# controller.net
KiCad netlist of a schematic drawn in EAGLE
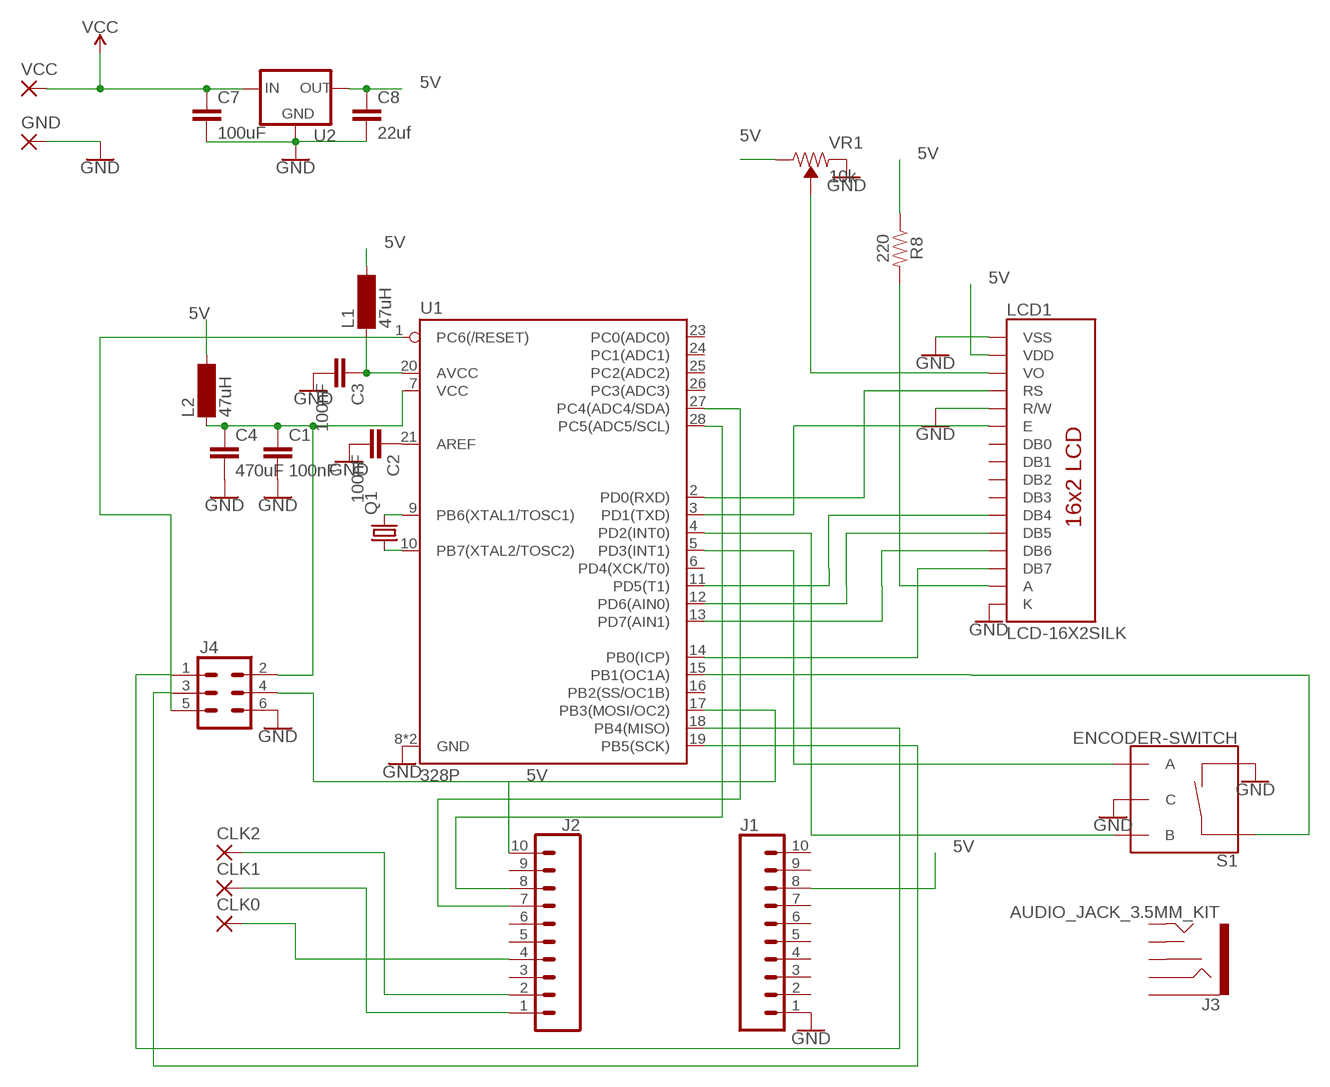
[diagram p0: schematic, sheet 1]

(export (version "E")
  (design (tool "Eeschema 10.0.6"))
  (components
    (comp (ref "C1")
      (value "100nF")
      (footprint "eagle-import:C5B3.5")
      (libsource (lib "eagle-import") (part "C5/3.5"))
    )
    (comp (ref "C2")
      (value "100nF")
      (footprint "eagle-import:C5B3.5")
      (libsource (lib "eagle-import") (part "C5/3.5"))
    )
    (comp (ref "C3")
      (value "100nF")
      (footprint "eagle-import:C5B3.5")
      (libsource (lib "eagle-import") (part "C5/3.5"))
    )
    (comp (ref "C4")
      (value "470uF")
      (footprint "eagle-import:C5B3.5")
      (libsource (lib "eagle-import") (part "C5/3.5"))
    )
    (comp (ref "C7")
      (value "100uF")
      (footprint "eagle-import:C5B3.5")
      (libsource (lib "eagle-import") (part "C5/3.5"))
    )
    (comp (ref "C8")
      (value "22uf")
      (footprint "eagle-import:C5B3.5")
      (libsource (lib "eagle-import") (part "C5/3.5"))
    )
    (comp (ref "CLK0")
      (value "3,17/1,1")
      (footprint "eagle-import:3,17_1,1")
      (libsource (lib "eagle-import") (part "3,17/1,1"))
    )
    (comp (ref "CLK1")
      (value "3,17/1,1")
      (footprint "eagle-import:3,17_1,1")
      (libsource (lib "eagle-import") (part "3,17/1,1"))
    )
    (comp (ref "CLK2")
      (value "3,17/1,1")
      (footprint "eagle-import:3,17_1,1")
      (libsource (lib "eagle-import") (part "3,17/1,1"))
    )
    (comp (ref "GND")
      (value "3,17/1,1")
      (footprint "eagle-import:3,17_1,1")
      (libsource (lib "eagle-import") (part "3,17/1,1"))
    )
    (comp (ref "J1")
      (value "CONN_10NO_SILK_PTH_FEMALE")
      (footprint "eagle-import:1X10_NO_SILK")
      (libsource (lib "eagle-import") (part "CONN_10NO_SILK_PTH_FEMALE"))
    )
    (comp (ref "J2")
      (value "CONN_10NO_SILK_PTH_FEMALE")
      (footprint "eagle-import:1X10_NO_SILK")
      (libsource (lib "eagle-import") (part "CONN_10NO_SILK_PTH_FEMALE"))
    )
    (comp (ref "J3")
      (value "AUDIO_JACK_3.5MM_KIT")
      (footprint "eagle-import:AUDIO-JACK-KIT")
      (libsource (lib "eagle-import") (part "AUDIO_JACK_3.5MM_KIT"))
    )
    (comp (ref "J4")
      (value "CONN_03X2NO_SILK")
      (footprint "eagle-import:2X3-NS")
      (libsource (lib "eagle-import") (part "CONN_03X2NO_SILK"))
    )
    (comp (ref "L1")
      (value "47uH")
      (footprint "eagle-import:BS75")
      (libsource (lib "eagle-import") (part "BS75"))
    )
    (comp (ref "L2")
      (value "47uH")
      (footprint "eagle-import:BS75")
      (libsource (lib "eagle-import") (part "BS75"))
    )
    (comp (ref "LCD1")
      (value "LCD-16X2SILK")
      (footprint "eagle-import:LCD-16X2")
      (libsource (lib "eagle-import") (part "LCD-16X2SILK"))
    )
    (comp (ref "Q1")
      (value "CRYTALHC49S")
      (footprint "eagle-import:HC49_S")
      (libsource (lib "eagle-import") (part "CRYTALHC49S"))
    )
    (comp (ref "R8")
      (value "220")
      (footprint "eagle-import:AXIAL-0.3")
      (libsource (lib "eagle-import") (part "1KOHM-HORIZ-1/4W-1%"))
    )
    (comp (ref "S1")
      (value "ENCODER-SWITCH")
      (footprint "eagle-import:ROTARY_ENC_PLAIN")
      (libsource (lib "eagle-import") (part "ENCODER-SWITCH"))
    )
    (comp (ref "U1")
      (value "328P")
      (footprint "eagle-import:DIP28")
      (libsource (lib "eagle-import") (part "ATMEGA328P_PDIP"))
    )
    (comp (ref "U2")
      (value "V_REG_78XXSINK")
      (footprint "eagle-import:TO220-IGO")
      (libsource (lib "eagle-import") (part "V_REG_78XXSINK"))
    )
    (comp (ref "VCC")
      (value "3,17/1,1")
      (footprint "eagle-import:3,17_1,1")
      (libsource (lib "eagle-import") (part "3,17/1,1"))
    )
    (comp (ref "VR1")
      (value "10k")
      (footprint "eagle-import:TRIMPOT-PTH-3386U")
      (libsource (lib "eagle-import") (part "TRIMPOT-PTH-10MM-KNOB-1/2W-10%"))
    )
  )
  (nets
    (net (code "1") (name "/5V") (class "Default")
      (node (ref "C8") (pin "1") (pinfunction "1_1") (pintype "passive"))
      (node (ref "J1") (pin "8") (pinfunction "8_8") (pintype "passive"))
      (node (ref "J2") (pin "10") (pinfunction "10_10") (pintype "passive"))
      (node (ref "L1") (pin "2") (pinfunction "2_2") (pintype "passive"))
      (node (ref "L2") (pin "2") (pinfunction "2_2") (pintype "passive"))
      (node (ref "LCD1") (pin "2") (pinfunction "VDD_2") (pintype "power_in"))
      (node (ref "R8") (pin "P$1") (pinfunction "1_P$1") (pintype "passive"))
      (node (ref "U2") (pin "OUT") (pinfunction "OUT_OUT") (pintype "passive"))
      (node (ref "VR1") (pin "3") (pinfunction "CW_3") (pintype "passive"))
    )
    (net (code "2") (name "GND") (class "Default")
      (node (ref "C1") (pin "2") (pinfunction "2_2") (pintype "passive"))
      (node (ref "C2") (pin "2") (pinfunction "2_2") (pintype "passive"))
      (node (ref "C3") (pin "2") (pinfunction "2_2") (pintype "passive"))
      (node (ref "C4") (pin "2") (pinfunction "2_2") (pintype "passive"))
      (node (ref "C7") (pin "2") (pinfunction "2_2") (pintype "passive"))
      (node (ref "C8") (pin "2") (pinfunction "2_2") (pintype "passive"))
      (node (ref "GND") (pin "1") (pinfunction "P_1") (pintype "passive"))
      (node (ref "J1") (pin "1") (pinfunction "1_1") (pintype "passive"))
      (node (ref "J4") (pin "6") (pinfunction "6_6") (pintype "bidirectional"))
      (node (ref "LCD1") (pin "1") (pinfunction "VSS_1") (pintype "power_in"))
      (node (ref "LCD1") (pin "16") (pinfunction "K_16") (pintype "power_in"))
      (node (ref "LCD1") (pin "5") (pinfunction "R/W_5") (pintype "input"))
      (node (ref "S1") (pin "C") (pinfunction "C_C") (pintype "bidirectional"))
      (node (ref "S1") (pin "SW-") (pinfunction "SW-_SW-") (pintype "bidirectional"))
      (node (ref "U1") (pin "22") (pinfunction "GND_22") (pintype "bidirectional"))
      (node (ref "U1") (pin "8") (pinfunction "GND_8") (pintype "bidirectional"))
      (node (ref "U2") (pin "GND") (pinfunction "GND_GND") (pintype "input"))
      (node (ref "VR1") (pin "1") (pinfunction "CCW_1") (pintype "passive"))
    )
    (net (code "3") (name "Net-(CLK0-P)") (class "Default")
      (node (ref "CLK0") (pin "1") (pinfunction "P_1") (pintype "passive"))
      (node (ref "J2") (pin "4") (pinfunction "4_4") (pintype "passive"))
    )
    (net (code "4") (name "Net-(CLK1-P)") (class "Default")
      (node (ref "CLK1") (pin "1") (pinfunction "P_1") (pintype "passive"))
      (node (ref "J2") (pin "1") (pinfunction "1_1") (pintype "passive"))
    )
    (net (code "5") (name "Net-(CLK2-P)") (class "Default")
      (node (ref "CLK2") (pin "1") (pinfunction "P_1") (pintype "passive"))
      (node (ref "J2") (pin "2") (pinfunction "2_2") (pintype "passive"))
    )
    (net (code "6") (name "Net-(LCD1-A)") (class "Default")
      (node (ref "LCD1") (pin "15") (pinfunction "A_15") (pintype "power_in"))
      (node (ref "R8") (pin "P$2") (pinfunction "2_P$2") (pintype "passive"))
    )
    (net (code "7") (name "Net-(LCD1-DB4)") (class "Default")
      (node (ref "LCD1") (pin "11") (pinfunction "DB4_11") (pintype "bidirectional"))
      (node (ref "U1") (pin "11") (pinfunction "PD5(T1)_11") (pintype "bidirectional"))
    )
    (net (code "8") (name "Net-(LCD1-DB5)") (class "Default")
      (node (ref "LCD1") (pin "12") (pinfunction "DB5_12") (pintype "bidirectional"))
      (node (ref "U1") (pin "12") (pinfunction "PD6(AIN0)_12") (pintype "bidirectional"))
    )
    (net (code "9") (name "Net-(LCD1-DB6)") (class "Default")
      (node (ref "LCD1") (pin "13") (pinfunction "DB6_13") (pintype "bidirectional"))
      (node (ref "U1") (pin "13") (pinfunction "PD7(AIN1)_13") (pintype "bidirectional"))
    )
    (net (code "10") (name "Net-(LCD1-DB7)") (class "Default")
      (node (ref "LCD1") (pin "14") (pinfunction "DB7_14") (pintype "bidirectional"))
      (node (ref "U1") (pin "14") (pinfunction "PB0(ICP)_14") (pintype "bidirectional"))
    )
    (net (code "11") (name "Net-(LCD1-E)") (class "Default")
      (node (ref "LCD1") (pin "6") (pinfunction "E_6") (pintype "input"))
      (node (ref "U1") (pin "3") (pinfunction "PD1(TXD)_3") (pintype "bidirectional"))
    )
    (net (code "12") (name "Net-(LCD1-RS)") (class "Default")
      (node (ref "LCD1") (pin "4") (pinfunction "RS_4") (pintype "input"))
      (node (ref "U1") (pin "2") (pinfunction "PD0(RXD)_2") (pintype "bidirectional"))
    )
    (net (code "13") (name "Net-(LCD1-VO)") (class "Default")
      (node (ref "LCD1") (pin "3") (pinfunction "VO_3") (pintype "bidirectional"))
      (node (ref "VR1") (pin "2") (pinfunction "WIPER_2") (pintype "passive"))
    )
    (net (code "14") (name "Net-(U1-AREF)") (class "Default")
      (node (ref "C2") (pin "1") (pinfunction "1_1") (pintype "passive"))
      (node (ref "U1") (pin "21") (pinfunction "AREF_21") (pintype "bidirectional"))
    )
    (net (code "15") (name "Net-(U1-AVCC)") (class "Default")
      (node (ref "C3") (pin "1") (pinfunction "1_1") (pintype "passive"))
      (node (ref "L1") (pin "1") (pinfunction "1_1") (pintype "passive"))
      (node (ref "U1") (pin "20") (pinfunction "AVCC_20") (pintype "bidirectional"))
    )
    (net (code "16") (name "Net-(U1-PB1(OC1A))") (class "Default")
      (node (ref "S1") (pin "SW+") (pinfunction "SW+_SW+") (pintype "bidirectional"))
      (node (ref "U1") (pin "15") (pinfunction "PB1(OC1A)_15") (pintype "bidirectional"))
    )
    (net (code "17") (name "Net-(U1-PB3(MOSI{slash}OC2))") (class "Default")
      (node (ref "J4") (pin "4") (pinfunction "4_4") (pintype "bidirectional"))
      (node (ref "U1") (pin "17") (pinfunction "PB3(MOSI/OC2)_17") (pintype "bidirectional"))
    )
    (net (code "18") (name "Net-(U1-PB4(MISO))") (class "Default")
      (node (ref "J4") (pin "1") (pinfunction "1_1") (pintype "bidirectional"))
      (node (ref "U1") (pin "18") (pinfunction "PB4(MISO)_18") (pintype "bidirectional"))
    )
    (net (code "19") (name "Net-(U1-PB5(SCK))") (class "Default")
      (node (ref "J4") (pin "3") (pinfunction "3_3") (pintype "bidirectional"))
      (node (ref "U1") (pin "19") (pinfunction "PB5(SCK)_19") (pintype "bidirectional"))
    )
    (net (code "20") (name "Net-(U1-PB6(XTAL1{slash}TOSC1))") (class "Default")
      (node (ref "Q1") (pin "2") (pinfunction "2_2") (pintype "passive"))
      (node (ref "U1") (pin "9") (pinfunction "PB6(XTAL1/TOSC1)_9") (pintype "bidirectional"))
    )
    (net (code "21") (name "Net-(U1-PB7(XTAL2{slash}TOSC2))") (class "Default")
      (node (ref "Q1") (pin "1") (pinfunction "1_1") (pintype "passive"))
      (node (ref "U1") (pin "10") (pinfunction "PB7(XTAL2/TOSC2)_10") (pintype "bidirectional"))
    )
    (net (code "22") (name "Net-(U1-PC4(ADC4{slash}SDA))") (class "Default")
      (node (ref "J2") (pin "7") (pinfunction "7_7") (pintype "passive"))
      (node (ref "U1") (pin "27") (pinfunction "PC4(ADC4/SDA)_27") (pintype "bidirectional"))
    )
    (net (code "23") (name "Net-(U1-PC5(ADC5{slash}SCL))") (class "Default")
      (node (ref "J2") (pin "8") (pinfunction "8_8") (pintype "passive"))
      (node (ref "U1") (pin "28") (pinfunction "PC5(ADC5/SCL)_28") (pintype "bidirectional"))
    )
    (net (code "24") (name "Net-(U1-PC6({slash}RESET))") (class "Default")
      (node (ref "J4") (pin "5") (pinfunction "5_5") (pintype "bidirectional"))
      (node (ref "U1") (pin "1") (pinfunction "PC6(/RESET)_1") (pintype "bidirectional"))
    )
    (net (code "25") (name "Net-(U1-PD2(INT0))") (class "Default")
      (node (ref "S1") (pin "B") (pinfunction "B_B") (pintype "bidirectional"))
      (node (ref "U1") (pin "4") (pinfunction "PD2(INT0)_4") (pintype "bidirectional"))
    )
    (net (code "26") (name "Net-(U1-PD3(INT1))") (class "Default")
      (node (ref "S1") (pin "A") (pinfunction "A_A") (pintype "bidirectional"))
      (node (ref "U1") (pin "5") (pinfunction "PD3(INT1)_5") (pintype "bidirectional"))
    )
    (net (code "27") (name "Net-(U1-VCC)") (class "Default")
      (node (ref "C1") (pin "1") (pinfunction "1_1") (pintype "passive"))
      (node (ref "C4") (pin "1") (pinfunction "1_1") (pintype "passive"))
      (node (ref "J4") (pin "2") (pinfunction "2_2") (pintype "bidirectional"))
      (node (ref "L2") (pin "1") (pinfunction "1_1") (pintype "passive"))
      (node (ref "U1") (pin "7") (pinfunction "VCC_7") (pintype "bidirectional"))
    )
    (net (code "28") (name "VCC") (class "Default")
      (node (ref "C7") (pin "1") (pinfunction "1_1") (pintype "passive"))
      (node (ref "U2") (pin "IN") (pinfunction "IN_IN") (pintype "input"))
      (node (ref "VCC") (pin "1") (pinfunction "P_1") (pintype "passive"))
    )
    (net (code "29") (name "unconnected-(J1-Pad2)") (class "Default")
      (node (ref "J1") (pin "2") (pinfunction "2_2") (pintype "passive"))
    )
    (net (code "30") (name "unconnected-(J1-Pad3)") (class "Default")
      (node (ref "J1") (pin "3") (pinfunction "3_3") (pintype "passive"))
    )
    (net (code "31") (name "unconnected-(J1-Pad4)") (class "Default")
      (node (ref "J1") (pin "4") (pinfunction "4_4") (pintype "passive"))
    )
    (net (code "32") (name "unconnected-(J1-Pad5)") (class "Default")
      (node (ref "J1") (pin "5") (pinfunction "5_5") (pintype "passive"))
    )
    (net (code "33") (name "unconnected-(J1-Pad6)") (class "Default")
      (node (ref "J1") (pin "6") (pinfunction "6_6") (pintype "passive"))
    )
    (net (code "34") (name "unconnected-(J1-Pad7)") (class "Default")
      (node (ref "J1") (pin "7") (pinfunction "7_7") (pintype "passive"))
    )
    (net (code "35") (name "unconnected-(J1-Pad9)") (class "Default")
      (node (ref "J1") (pin "9") (pinfunction "9_9") (pintype "passive"))
    )
    (net (code "36") (name "unconnected-(J1-Pad10)") (class "Default")
      (node (ref "J1") (pin "10") (pinfunction "10_10") (pintype "passive"))
    )
    (net (code "37") (name "unconnected-(J2-Pad3)") (class "Default")
      (node (ref "J2") (pin "3") (pinfunction "3_3") (pintype "passive"))
    )
    (net (code "38") (name "unconnected-(J2-Pad5)") (class "Default")
      (node (ref "J2") (pin "5") (pinfunction "5_5") (pintype "passive"))
    )
    (net (code "39") (name "unconnected-(J2-Pad6)") (class "Default")
      (node (ref "J2") (pin "6") (pinfunction "6_6") (pintype "passive"))
    )
    (net (code "40") (name "unconnected-(J2-Pad9)") (class "Default")
      (node (ref "J2") (pin "9") (pinfunction "9_9") (pintype "passive"))
    )
    (net (code "41") (name "unconnected-(J3-PadRING)") (class "Default")
      (node (ref "J3") (pin "RING") (pinfunction "RING_RING") (pintype "bidirectional"))
    )
    (net (code "42") (name "unconnected-(J3-PadRSH)") (class "Default")
      (node (ref "J3") (pin "RSH") (pinfunction "RSH_RSH") (pintype "bidirectional"))
    )
    (net (code "43") (name "unconnected-(J3-PadSLEEVE)") (class "Default")
      (node (ref "J3") (pin "SLEEVE") (pinfunction "SLEEVE_SLEEVE") (pintype "bidirectional"))
    )
    (net (code "44") (name "unconnected-(J3-PadTIP)") (class "Default")
      (node (ref "J3") (pin "TIP") (pinfunction "TIP_TIP") (pintype "bidirectional"))
    )
    (net (code "45") (name "unconnected-(J3-PadTSH)") (class "Default")
      (node (ref "J3") (pin "TSH") (pinfunction "TSH_TSH") (pintype "bidirectional"))
    )
    (net (code "46") (name "unconnected-(LCD1-DB0-Pad7)") (class "Default")
      (node (ref "LCD1") (pin "7") (pinfunction "DB0_7") (pintype "bidirectional"))
    )
    (net (code "47") (name "unconnected-(LCD1-DB1-Pad8)") (class "Default")
      (node (ref "LCD1") (pin "8") (pinfunction "DB1_8") (pintype "bidirectional"))
    )
    (net (code "48") (name "unconnected-(LCD1-DB2-Pad9)") (class "Default")
      (node (ref "LCD1") (pin "9") (pinfunction "DB2_9") (pintype "bidirectional"))
    )
    (net (code "49") (name "unconnected-(LCD1-DB3-Pad10)") (class "Default")
      (node (ref "LCD1") (pin "10") (pinfunction "DB3_10") (pintype "bidirectional"))
    )
    (net (code "50") (name "unconnected-(U1-PB2(SS{slash}OC1B)-Pad16)") (class "Default")
      (node (ref "U1") (pin "16") (pinfunction "PB2(SS/OC1B)_16") (pintype "bidirectional"))
    )
    (net (code "51") (name "unconnected-(U1-PC0(ADC0)-Pad23)") (class "Default")
      (node (ref "U1") (pin "23") (pinfunction "PC0(ADC0)_23") (pintype "bidirectional"))
    )
    (net (code "52") (name "unconnected-(U1-PC1(ADC1)-Pad24)") (class "Default")
      (node (ref "U1") (pin "24") (pinfunction "PC1(ADC1)_24") (pintype "bidirectional"))
    )
    (net (code "53") (name "unconnected-(U1-PC2(ADC2)-Pad25)") (class "Default")
      (node (ref "U1") (pin "25") (pinfunction "PC2(ADC2)_25") (pintype "bidirectional"))
    )
    (net (code "54") (name "unconnected-(U1-PC3(ADC3)-Pad26)") (class "Default")
      (node (ref "U1") (pin "26") (pinfunction "PC3(ADC3)_26") (pintype "bidirectional"))
    )
    (net (code "55") (name "unconnected-(U1-PD4(XCK{slash}T0)-Pad6)") (class "Default")
      (node (ref "U1") (pin "6") (pinfunction "PD4(XCK/T0)_6") (pintype "bidirectional"))
    )
  )
)
